# 09_USB_HUB.net
KiCad netlist of a schematic drawn in Altium Designer
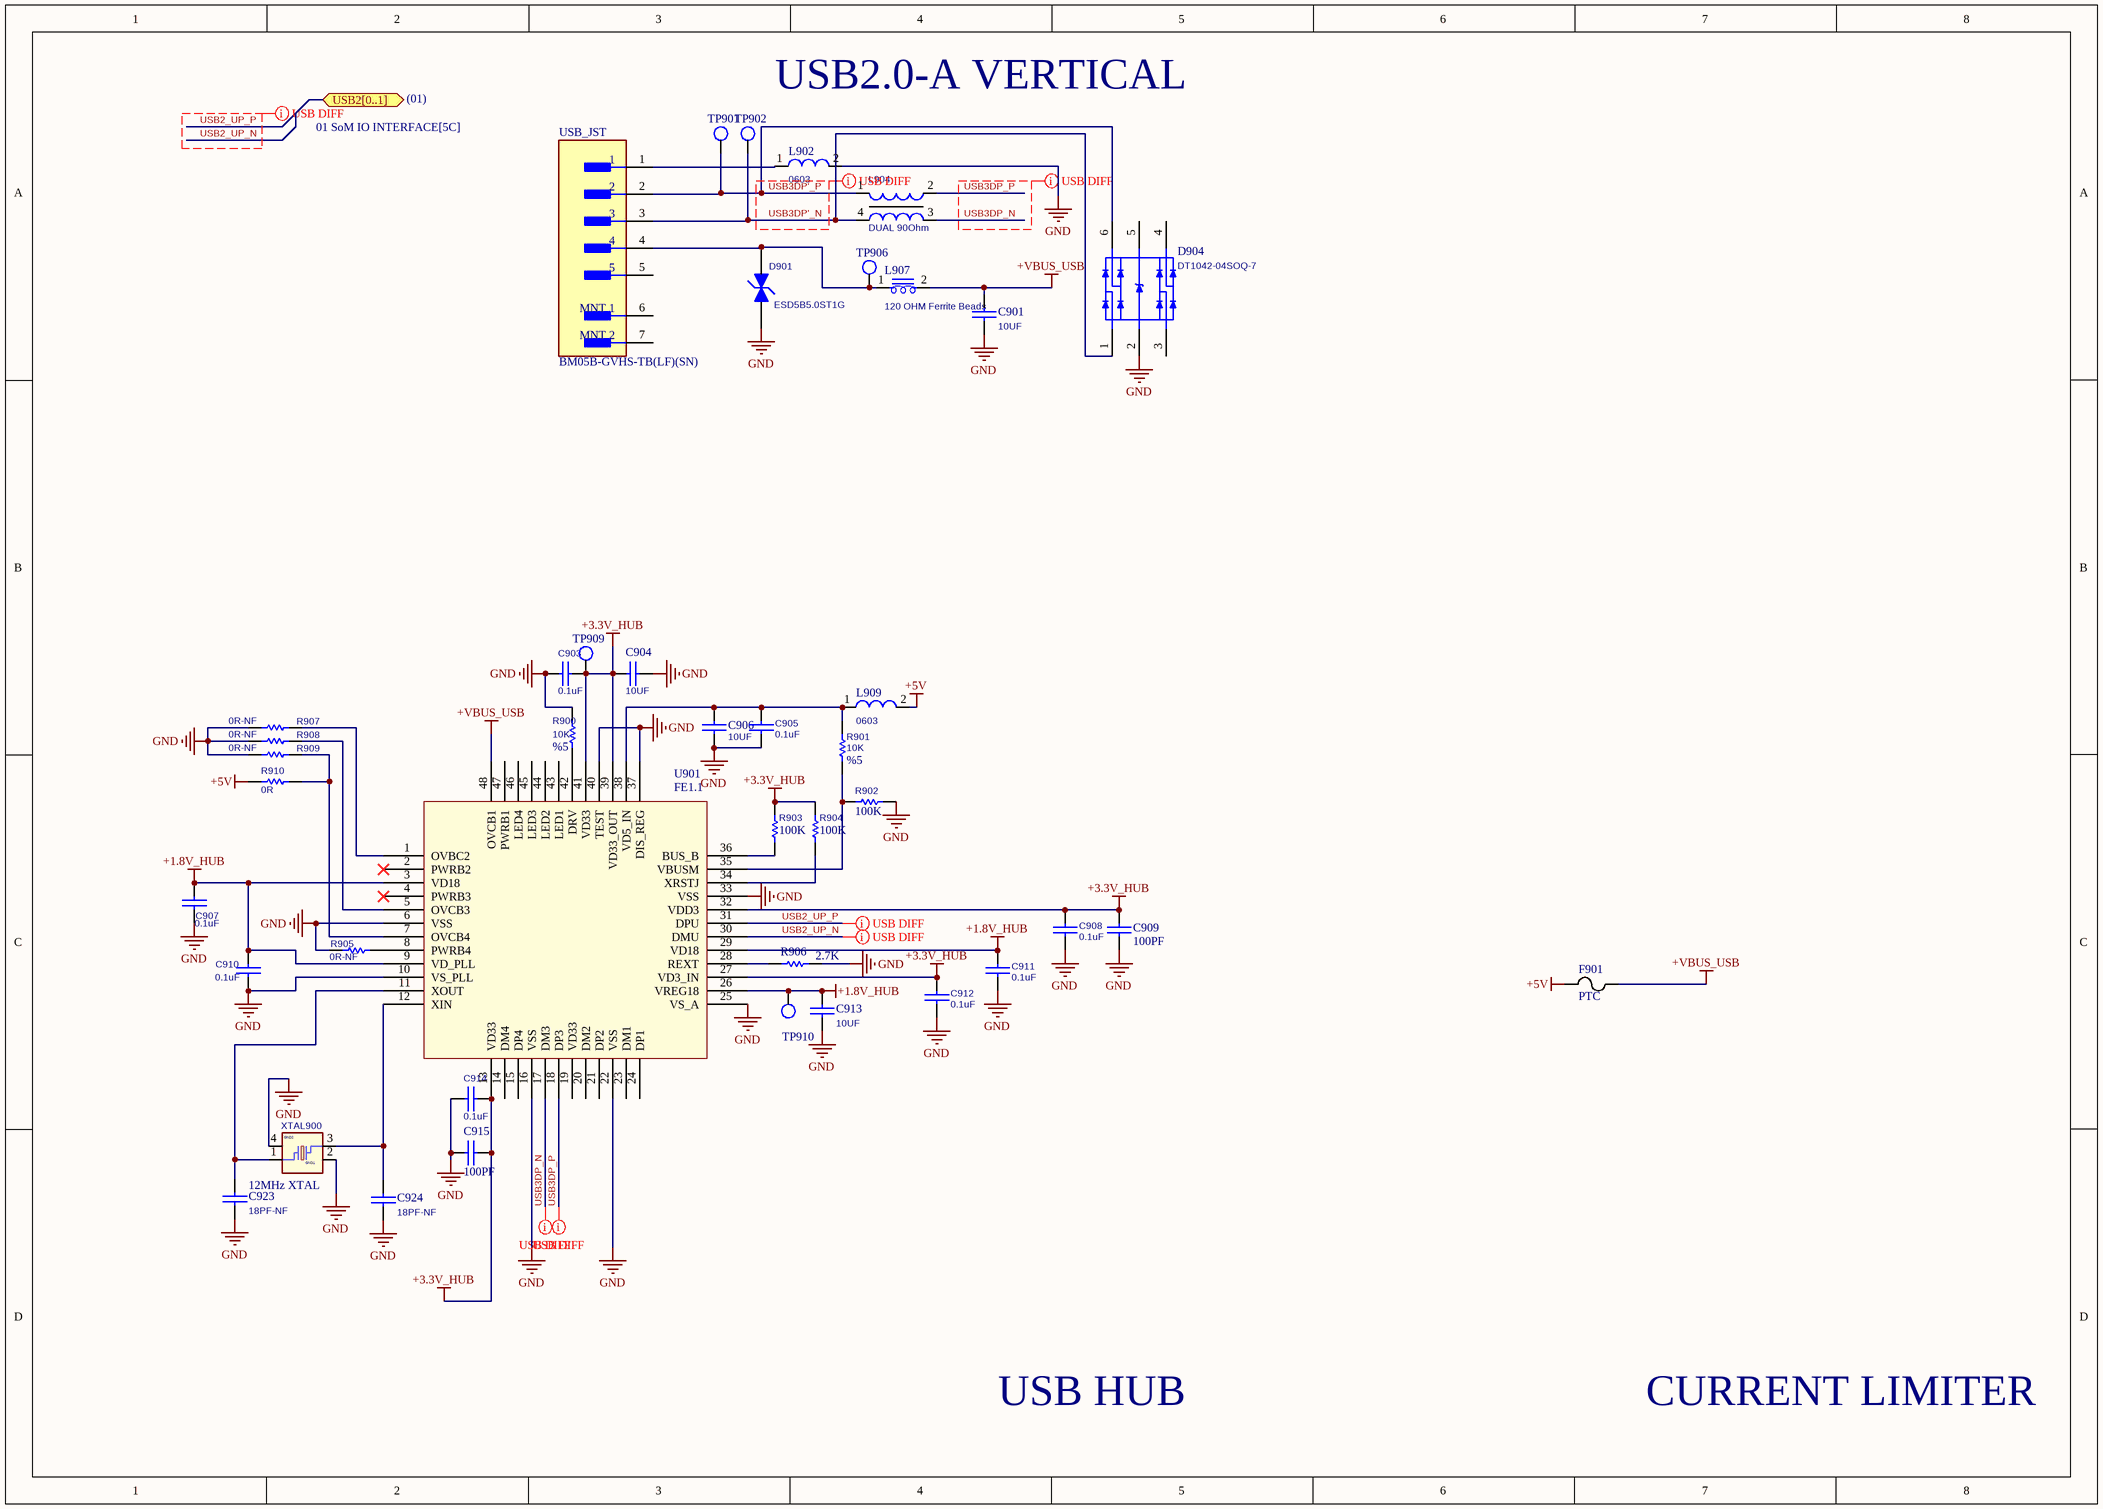
[diagram p0: 09 USB HUB.SchDoc]

(export (version "E")
  (design (tool "Eeschema 10.0.6"))
  (components
    (comp (ref "C901")
      (value "10UF")
      (footprint "0805")
      (description "CAP CER 10UF 16V X5R 0805")
      (fields (field (name "CREATED BY") "EE") (field (name "CHECKED BY") "*"))
      (libsource (lib "ARETE_SCH") (part "CAP-CL21A106KOQNNNG"))
    )
    (comp (ref "C903")
      (value "0.1uF")
      (footprint "0402_CC")
      (description "CAP VER 0.1UF 16V X7R 0402")
      (fields (field (name "CREATED BY") "LA") (field (name "CHECKED BY") "*"))
      (libsource (lib "ARETE_SCH") (part "CAP-CL05B104KO5NNNC"))
    )
    (comp (ref "C904")
      (value "10UF")
      (footprint "0805")
      (description "CAP CER 10UF 16V X5R 0805")
      (fields (field (name "CREATED BY") "EE") (field (name "CHECKED BY") "*"))
      (libsource (lib "ARETE_SCH") (part "CAP-CL21A106KOQNNNG"))
    )
    (comp (ref "C905")
      (value "0.1uF")
      (footprint "0402_CC")
      (description "CAP VER 0.1UF 16V X7R 0402")
      (fields (field (name "CREATED BY") "LA") (field (name "CHECKED BY") "*"))
      (libsource (lib "ARETE_SCH") (part "CAP-CL05B104KO5NNNC"))
    )
    (comp (ref "C906")
      (value "10UF")
      (footprint "0805")
      (description "CAP CER 10UF 16V X5R 0805")
      (fields (field (name "CREATED BY") "EE") (field (name "CHECKED BY") "*"))
      (libsource (lib "ARETE_SCH") (part "CAP-CL21A106KOQNNNG"))
    )
    (comp (ref "C907")
      (value "0.1uF")
      (footprint "0402_CC")
      (description "CAP VER 0.1UF 16V X7R 0402")
      (fields (field (name "CREATED BY") "LA") (field (name "CHECKED BY") "*"))
      (libsource (lib "ARETE_SCH") (part "CAP-CL05B104KO5NNNC"))
    )
    (comp (ref "C908")
      (value "0.1uF")
      (footprint "0402_CC")
      (description "CAP VER 0.1UF 16V X7R 0402")
      (fields (field (name "CREATED BY") "LA") (field (name "CHECKED BY") "*"))
      (libsource (lib "ARETE_SCH") (part "CAP-CL05B104KO5NNNC"))
    )
    (comp (ref "C909")
      (value "100PF")
      (footprint "0402_CC")
      (description "CAP CER 100PF 50V C0G/NPO 0402")
      (fields (field (name "CREATED BY") "*") (field (name "CHECKED BY") "*"))
      (libsource (lib "ARETE_SCH") (part "CAP-CC0402JRNPO9BN101"))
    )
    (comp (ref "C910")
      (value "0.1uF")
      (footprint "0402_CC")
      (description "CAP VER 0.1UF 16V X7R 0402")
      (fields (field (name "CREATED BY") "LA") (field (name "CHECKED BY") "*"))
      (libsource (lib "ARETE_SCH") (part "CAP-CL05B104KO5NNNC"))
    )
    (comp (ref "C911")
      (value "0.1uF")
      (footprint "0402_CC")
      (description "CAP VER 0.1UF 16V X7R 0402")
      (fields (field (name "CREATED BY") "LA") (field (name "CHECKED BY") "*"))
      (libsource (lib "ARETE_SCH") (part "CAP-CL05B104KO5NNNC"))
    )
    (comp (ref "C912")
      (value "0.1uF")
      (footprint "0402_CC")
      (description "CAP VER 0.1UF 16V X7R 0402")
      (fields (field (name "CREATED BY") "LA") (field (name "CHECKED BY") "*"))
      (libsource (lib "ARETE_SCH") (part "CAP-CL05B104KO5NNNC"))
    )
    (comp (ref "C913")
      (value "10UF")
      (footprint "0805")
      (description "CAP CER 10UF 16V X5R 0805")
      (fields (field (name "CREATED BY") "EE") (field (name "CHECKED BY") "*"))
      (libsource (lib "ARETE_SCH") (part "CAP-CL21A106KOQNNNG"))
    )
    (comp (ref "C914")
      (value "0.1uF")
      (footprint "0402_CC")
      (description "CAP VER 0.1UF 16V X7R 0402")
      (fields (field (name "CREATED BY") "LA") (field (name "CHECKED BY") "*"))
      (libsource (lib "ARETE_SCH") (part "CAP-CL05B104KO5NNNC"))
    )
    (comp (ref "C915")
      (value "100PF")
      (footprint "0402_CC")
      (description "CAP CER 100PF 50V C0G/NPO 0402")
      (fields (field (name "CREATED BY") "*") (field (name "CHECKED BY") "*"))
      (libsource (lib "ARETE_SCH") (part "CAP-CC0402JRNPO9BN101"))
    )
    (comp (ref "C923")
      (value "18PF-NF")
      (footprint "0402_CC")
      (description "CAP CER 18PF 50V C0G/NP0 0402")
      (fields (field (name "CREATED BY") "*") (field (name "CHECKED BY") "*"))
      (libsource (lib "ARETE_SCH") (part "CAP-GCM1555C1H180JA16D"))
    )
    (comp (ref "C924")
      (value "18PF-NF")
      (footprint "0402_CC")
      (description "CAP CER 18PF 50V C0G/NP0 0402")
      (fields (field (name "CREATED BY") "*") (field (name "CHECKED BY") "*"))
      (libsource (lib "ARETE_SCH") (part "CAP-GCM1555C1H180JA16D"))
    )
    (comp (ref "D901")
      (value "ESD5B5.0ST1G")
      (footprint "SOD523 - SZESD")
      (description "VS DIODE 5V SOD523")
      (fields (field (name "CREATED BY") "E.E") (field (name "CHECKED BY") "*"))
      (libsource (lib "ARETE_SCH") (part "DIODE-ESD5B5.0ST1G"))
    )
    (comp (ref "D904")
      (value "DT1042-04SOQ-7")
      (footprint "DIODE-DT1042-04SOQ-7")
      (description "HDMI TVS DIODE")
      (fields (field (name "CREATED BY") "E.E") (field (name "CHECKED BY") "*"))
      (libsource (lib "ARETE_SCH") (part "DIODE-DT1042-04SOQ-7"))
    )
    (comp (ref "F901")
      (value "PTC")
      (footprint "1812")
      (description "THERMISTOR PTC RESETTABLE FUSE 1206 1100mA 33V 1812")
      (fields (field (name "CREATED BY") "EE") (field (name "CHECKED BY") "*"))
      (libsource (lib "ARETE_V2_SCH") (part "FUSE-KMC5S110RY33"))
    )
    (comp (ref "L902")
      (value "0603")
      (footprint "0603_RES")
      (description "0OHM 0603")
      (fields (field (name "CREATED BY") "EE") (field (name "CHECKED BY") "*"))
      (libsource (lib "ARETE_SCH") (part "IND-FERRITE (RES 0 OHM) 0603"))
    )
    (comp (ref "L904")
      (value "DUAL 90Ohm")
      (footprint "DLW21H")
      (description "Common Mode Chokes Dual 90Ohm 100MHz 0.33A 0.35Ohm DCR SMD T/R")
      (fields (field (name "CREATED BY") "E.E") (field (name "CHECKED BY") "*"))
      (libsource (lib "ARETE_SCH") (part "IND-DLW21HN900SQ2L"))
    )
    (comp (ref "L907")
      (value "120 OHM Ferrite Beads")
      (footprint "0603_RES")
      (description "Ferrite Beads Multi-Layer 120Ohm 25% 100MHz 2A 0.05Ohm DCR 0603 Automotive T/R")
      (fields (field (name "CREATED BY") "E.E") (field (name "CHECKED BY") "*"))
      (libsource (lib "ARETE_SCH") (part "IND-BLM18PG121SH1D"))
    )
    (comp (ref "L909")
      (value "0603")
      (footprint "0603_RES")
      (description "0OHM 0603")
      (fields (field (name "CREATED BY") "EE") (field (name "CHECKED BY") "*"))
      (libsource (lib "ARETE_SCH") (part "IND-FERRITE (RES 0 OHM) 0603"))
    )
    (comp (ref "R900")
      (value "10K")
      (footprint "0402_RES")
      (description "RES 10K OHM 5% 1/16W 0402")
      (fields
        (field (name "TOLERANCE") "%5")
        (field (name "CREATED BY") "LA")
        (field (name "CHECKED BY") "*")
      )
      (libsource (lib "ARETE_SCH") (part "RES-RMCF0402JT10K0"))
    )
    (comp (ref "R901")
      (value "10K")
      (footprint "0402_RES")
      (description "RES 10K OHM 5% 1/16W 0402")
      (fields
        (field (name "TOLERANCE") "%5")
        (field (name "CREATED BY") "LA")
        (field (name "CHECKED BY") "*")
      )
      (libsource (lib "ARETE_SCH") (part "RES-RMCF0402JT10K0"))
    )
    (comp (ref "R902")
      (value "100K")
      (footprint "0402_RES")
      (description "RES 100K OHM 5% 1/16W 0402")
      (fields
        (field (name "TOLERANCE") "%5")
        (field (name "CREATED BY") "LA")
        (field (name "CHECKED BY") "*")
      )
      (libsource (lib "ARETE_SCH") (part "RES-RMCF0402JT100K"))
    )
    (comp (ref "R903")
      (value "100K")
      (footprint "0402_RES")
      (description "RES 100K OHM 5% 1/16W 0402")
      (fields
        (field (name "TOLERANCE") "%5")
        (field (name "CREATED BY") "LA")
        (field (name "CHECKED BY") "*")
      )
      (libsource (lib "ARETE_SCH") (part "RES-RMCF0402JT100K"))
    )
    (comp (ref "R904")
      (value "100K")
      (footprint "0402_RES")
      (description "RES 100K OHM 5% 1/16W 0402")
      (fields
        (field (name "TOLERANCE") "%5")
        (field (name "CREATED BY") "LA")
        (field (name "CHECKED BY") "*")
      )
      (libsource (lib "ARETE_SCH") (part "RES-RMCF0402JT100K"))
    )
    (comp (ref "R905")
      (value "0R-NF")
      (footprint "0402_RES")
      (description "RES 0 OHM JUMPER 1/16W 0402")
      (fields (field (name "CREATED BY") "LA") (field (name "CHECKED BY") "*"))
      (libsource (lib "ARETE_SCH") (part "RES-RMCF0402ZT0R00"))
    )
    (comp (ref "R906")
      (value "2.7K")
      (footprint "0402_RES")
      (description "RES SMD 2.7K OHM 1% 1/16W 0402")
      (fields (field (name "CREATED BY") "EE") (field (name "CHECKED BY") "*"))
      (libsource (lib "ARETE_V2_SCH") (part "RES-RMCF0402FT2K70"))
    )
    (comp (ref "R907")
      (value "0R-NF")
      (footprint "0402_RES")
      (description "RES 0 OHM JUMPER 1/16W 0402")
      (fields (field (name "CREATED BY") "LA") (field (name "CHECKED BY") "*"))
      (libsource (lib "ARETE_SCH") (part "RES-RMCF0402ZT0R00"))
    )
    (comp (ref "R908")
      (value "0R-NF")
      (footprint "0402_RES")
      (description "RES 0 OHM JUMPER 1/16W 0402")
      (fields (field (name "CREATED BY") "LA") (field (name "CHECKED BY") "*"))
      (libsource (lib "ARETE_SCH") (part "RES-RMCF0402ZT0R00"))
    )
    (comp (ref "R909")
      (value "0R-NF")
      (footprint "0402_RES")
      (description "RES 0 OHM JUMPER 1/16W 0402")
      (fields (field (name "CREATED BY") "LA") (field (name "CHECKED BY") "*"))
      (libsource (lib "ARETE_SCH") (part "RES-RMCF0402ZT0R00"))
    )
    (comp (ref "R910")
      (value "0R")
      (footprint "0402_RES")
      (description "RES 0 OHM JUMPER 1/16W 0402")
      (fields (field (name "CREATED BY") "LA") (field (name "CHECKED BY") "*"))
      (libsource (lib "ARETE_SCH") (part "RES-RMCF0402ZT0R00"))
    )
    (comp (ref "TP901")
      (value "TEST POINT 15")
      (footprint "testpoint_15")
      (libsource (lib "X98_CARRIER_V1R2") (part "TEST POINT 15"))
    )
    (comp (ref "TP902")
      (value "TEST POINT 15")
      (footprint "testpoint_15")
      (libsource (lib "X98_CARRIER_V1R2") (part "TEST POINT 15"))
    )
    (comp (ref "TP906")
      (value "TEST POINT 15")
      (footprint "testpoint_15")
      (libsource (lib "X98_CARRIER_V1R2") (part "TEST POINT 15"))
    )
    (comp (ref "TP909")
      (value "TEST POINT 15")
      (footprint "testpoint_15")
      (libsource (lib "X98_CARRIER_V1R2") (part "TEST POINT 15"))
    )
    (comp (ref "TP910")
      (value "TEST POINT 15")
      (footprint "testpoint_15")
      (libsource (lib "X98_CARRIER_V1R2") (part "TEST POINT 15"))
    )
    (comp (ref "U901")
      (value "FE1.1")
      (footprint "LQFP48")
      (description "IC 4XCH USB Hub Controller USB 2.0 USB Interface 48-QFP (7x7)")
      (fields (field (name "CREATED BY") "OKS") (field (name "CHECKED BY") "*"))
      (libsource (lib "ARETE_V2_SCH") (part "IC-FE1.1-AQFP48A"))
    )
    (comp (ref "USB_JST")
      (value "BM05B-GVHS-TB(LF)(SN)")
      (footprint "FP-BM05B-GVHS-TB_LF_SN-MFG")
      (description "CONN HEADER SMD 5POS 1.25MM")
      (libsource (lib "Altium Content Vault") (part "a8463467369b6bfccc80258e24cb490"))
    )
    (comp (ref "XTAL900")
      (value "CRYSTAL 12.MHZ 18PF SMD")
      (footprint "XTLOSC4_3P2X2P5MM_SM")
      (description "CRYSTAL 12.0000MHZ 18PF SMD")
      (fields (field (name "CREATED BY") "E.E") (field (name "CHECKED BY") "*"))
      (libsource (lib "ARETE_SCH") (part "XTAL-FA-238V 12.0000MB50X-C0"))
    )
  )
  (nets
    (net (code "3") (name "+1.8V_HUB") (class "Default")
      (node (ref "C907") (pin "1") (pinfunction "1_1") (pintype "passive"))
      (node (ref "C910") (pin "1") (pinfunction "1_1") (pintype "passive"))
      (node (ref "C911") (pin "2") (pinfunction "2_2") (pintype "passive"))
      (node (ref "C913") (pin "1") (pinfunction "1_1") (pintype "passive"))
      (node (ref "TP910") (pin "1") (pinfunction "1_1") (pintype "passive"))
      (node (ref "U901") (pin "26") (pinfunction "VREG18_26") (pintype "passive"))
      (node (ref "U901") (pin "29") (pinfunction "VD18_29") (pintype "passive"))
      (node (ref "U901") (pin "3") (pinfunction "VD18_3") (pintype "passive"))
      (node (ref "U901") (pin "9") (pinfunction "VD_PLL_9") (pintype "passive"))
    )
    (net (code "4") (name "+3.3V_HUB") (class "Default")
      (node (ref "C903") (pin "1") (pinfunction "1_1") (pintype "passive"))
      (node (ref "C904") (pin "1") (pinfunction "1_1") (pintype "passive"))
      (node (ref "C908") (pin "2") (pinfunction "2_2") (pintype "passive"))
      (node (ref "C909") (pin "2") (pinfunction "2_2") (pintype "passive"))
      (node (ref "C912") (pin "2") (pinfunction "2_2") (pintype "passive"))
      (node (ref "C914") (pin "2") (pinfunction "2_2") (pintype "passive"))
      (node (ref "C915") (pin "2") (pinfunction "2_2") (pintype "passive"))
      (node (ref "R903") (pin "2") (pinfunction "2_2") (pintype "passive"))
      (node (ref "R904") (pin "2") (pinfunction "2_2") (pintype "passive"))
      (node (ref "TP909") (pin "1") (pinfunction "1_1") (pintype "passive"))
      (node (ref "U901") (pin "13") (pinfunction "VD33_13") (pintype "passive"))
      (node (ref "U901") (pin "27") (pinfunction "VD3_IN_27") (pintype "passive"))
      (node (ref "U901") (pin "32") (pinfunction "VDD3_32") (pintype "passive"))
      (node (ref "U901") (pin "39") (pinfunction "VD33_OUT_39") (pintype "passive"))
      (node (ref "U901") (pin "41") (pinfunction "VD33_41") (pintype "passive"))
    )
    (net (code "5") (name "+5V") (class "Default")
      (node (ref "F901") (pin "1") (pinfunction "1_1") (pintype "passive"))
      (node (ref "L909") (pin "2") (pinfunction "2_2") (pintype "passive"))
      (node (ref "R910") (pin "2") (pinfunction "2_2") (pintype "passive"))
    )
    (net (code "6") (name "+VBUS_USB") (class "Default")
      (node (ref "C901") (pin "1") (pinfunction "1_1") (pintype "passive"))
      (node (ref "F901") (pin "2") (pinfunction "2_2") (pintype "passive"))
      (node (ref "L907") (pin "2") (pinfunction "2_2") (pintype "passive"))
      (node (ref "U901") (pin "48") (pinfunction "OVCB1_48") (pintype "passive"))
    )
    (net (code "8") (name "/USB2_UP_N") (class "Default")
      (node (ref "U901") (pin "30") (pinfunction "DMU_30") (pintype "passive"))
    )
    (net (code "9") (name "/USB2_UP_P") (class "Default")
      (node (ref "U901") (pin "31") (pinfunction "DPU_31") (pintype "passive"))
    )
    (net (code "10") (name "/USB3DP'_N") (class "Default")
      (node (ref "D904") (pin "1") (pinfunction "IO1_1") (pintype "passive"))
      (node (ref "L904") (pin "4") (pinfunction "4_4") (pintype "passive"))
      (node (ref "TP902") (pin "1") (pinfunction "1_1") (pintype "passive"))
      (node (ref "USB_JST") (pin "3") (pinfunction "3_3") (pintype "passive"))
    )
    (net (code "11") (name "/USB3DP'_P") (class "Default")
      (node (ref "D904") (pin "6") (pinfunction "IO4_6") (pintype "passive"))
      (node (ref "L904") (pin "1") (pinfunction "1_1") (pintype "passive"))
      (node (ref "TP901") (pin "1") (pinfunction "1_1") (pintype "passive"))
      (node (ref "USB_JST") (pin "2") (pinfunction "2_2") (pintype "passive"))
    )
    (net (code "12") (name "/USB3DP_N") (class "Default")
      (node (ref "L904") (pin "3") (pinfunction "3_3") (pintype "passive"))
      (node (ref "U901") (pin "17") (pinfunction "DM3_17") (pintype "passive"))
    )
    (net (code "13") (name "/USB3DP_P") (class "Default")
      (node (ref "L904") (pin "2") (pinfunction "2_2") (pintype "passive"))
      (node (ref "U901") (pin "18") (pinfunction "DP3_18") (pintype "passive"))
    )
    (net (code "14") (name "GND") (class "Default")
      (node (ref "C901") (pin "2") (pinfunction "2_2") (pintype "passive"))
      (node (ref "C903") (pin "2") (pinfunction "2_2") (pintype "passive"))
      (node (ref "C904") (pin "2") (pinfunction "2_2") (pintype "passive"))
      (node (ref "C905") (pin "1") (pinfunction "1_1") (pintype "passive"))
      (node (ref "C906") (pin "1") (pinfunction "1_1") (pintype "passive"))
      (node (ref "C907") (pin "2") (pinfunction "2_2") (pintype "passive"))
      (node (ref "C908") (pin "1") (pinfunction "1_1") (pintype "passive"))
      (node (ref "C909") (pin "1") (pinfunction "1_1") (pintype "passive"))
      (node (ref "C910") (pin "2") (pinfunction "2_2") (pintype "passive"))
      (node (ref "C911") (pin "1") (pinfunction "1_1") (pintype "passive"))
      (node (ref "C912") (pin "1") (pinfunction "1_1") (pintype "passive"))
      (node (ref "C913") (pin "2") (pinfunction "2_2") (pintype "passive"))
      (node (ref "C914") (pin "1") (pinfunction "1_1") (pintype "passive"))
      (node (ref "C915") (pin "1") (pinfunction "1_1") (pintype "passive"))
      (node (ref "C923") (pin "2") (pinfunction "2_2") (pintype "passive"))
      (node (ref "C924") (pin "2") (pinfunction "2_2") (pintype "passive"))
      (node (ref "D901") (pin "1") (pinfunction "A_1") (pintype "passive"))
      (node (ref "D904") (pin "2") (pinfunction "VSS_2") (pintype "power_in"))
      (node (ref "L902") (pin "2") (pinfunction "2_2") (pintype "passive"))
      (node (ref "R900") (pin "1") (pinfunction "1_1") (pintype "passive"))
      (node (ref "R902") (pin "1") (pinfunction "1_1") (pintype "passive"))
      (node (ref "R905") (pin "1") (pinfunction "1_1") (pintype "passive"))
      (node (ref "R906") (pin "2") (pinfunction "2_2") (pintype "passive"))
      (node (ref "R907") (pin "1") (pinfunction "1_1") (pintype "passive"))
      (node (ref "R908") (pin "1") (pinfunction "1_1") (pintype "passive"))
      (node (ref "R909") (pin "1") (pinfunction "1_1") (pintype "passive"))
      (node (ref "U901") (pin "10") (pinfunction "VS_PLL_10") (pintype "passive"))
      (node (ref "U901") (pin "16") (pinfunction "VSS_16") (pintype "passive"))
      (node (ref "U901") (pin "22") (pinfunction "VSS_22") (pintype "passive"))
      (node (ref "U901") (pin "25") (pinfunction "VS_A_25") (pintype "passive"))
      (node (ref "U901") (pin "33") (pinfunction "VSS_33") (pintype "passive"))
      (node (ref "U901") (pin "37") (pinfunction "DIS_REG_37") (pintype "passive"))
      (node (ref "U901") (pin "40") (pinfunction "TEST_40") (pintype "passive"))
      (node (ref "U901") (pin "6") (pinfunction "VSS_6") (pintype "passive"))
      (node (ref "XTAL900") (pin "2") (pinfunction "GND1_2") (pintype "power_in"))
      (node (ref "XTAL900") (pin "4") (pinfunction "GND2_4") (pintype "power_in"))
    )
    (net (code "15") (name "Net-(D901-K)") (class "Default")
      (node (ref "D901") (pin "2") (pinfunction "K_2") (pintype "passive"))
      (node (ref "L907") (pin "1") (pinfunction "1_1") (pintype "passive"))
      (node (ref "TP906") (pin "1") (pinfunction "1_1") (pintype "passive"))
      (node (ref "USB_JST") (pin "4") (pinfunction "4_4") (pintype "passive"))
    )
    (net (code "16") (name "Net-(L902-Pad1)") (class "Default")
      (node (ref "L902") (pin "1") (pinfunction "1_1") (pintype "passive"))
      (node (ref "USB_JST") (pin "1") (pinfunction "1_1") (pintype "passive"))
    )
    (net (code "17") (name "Net-(U901-BUS_B)") (class "Default")
      (node (ref "R903") (pin "1") (pinfunction "1_1") (pintype "passive"))
      (node (ref "U901") (pin "36") (pinfunction "BUS_B_36") (pintype "passive"))
    )
    (net (code "18") (name "Net-(U901-DRV)") (class "Default")
      (node (ref "R900") (pin "2") (pinfunction "2_2") (pintype "passive"))
      (node (ref "U901") (pin "42") (pinfunction "DRV_42") (pintype "passive"))
    )
    (net (code "19") (name "Net-(U901-OVBC2)") (class "Default")
      (node (ref "R907") (pin "2") (pinfunction "2_2") (pintype "passive"))
      (node (ref "U901") (pin "1") (pinfunction "OVBC2_1") (pintype "passive"))
    )
    (net (code "20") (name "Net-(U901-OVCB3)") (class "Default")
      (node (ref "R908") (pin "2") (pinfunction "2_2") (pintype "passive"))
      (node (ref "U901") (pin "5") (pinfunction "OVCB3_5") (pintype "passive"))
    )
    (net (code "21") (name "Net-(U901-OVCB4)") (class "Default")
      (node (ref "R909") (pin "2") (pinfunction "2_2") (pintype "passive"))
      (node (ref "R910") (pin "1") (pinfunction "1_1") (pintype "passive"))
      (node (ref "U901") (pin "7") (pinfunction "OVCB4_7") (pintype "passive"))
    )
    (net (code "22") (name "Net-(U901-PWRB4)") (class "Default")
      (node (ref "R905") (pin "2") (pinfunction "2_2") (pintype "passive"))
      (node (ref "U901") (pin "8") (pinfunction "PWRB4_8") (pintype "passive"))
    )
    (net (code "23") (name "Net-(U901-REXT)") (class "Default")
      (node (ref "R906") (pin "1") (pinfunction "1_1") (pintype "passive"))
      (node (ref "U901") (pin "28") (pinfunction "REXT_28") (pintype "passive"))
    )
    (net (code "24") (name "Net-(U901-VBUSM)") (class "Default")
      (node (ref "R901") (pin "1") (pinfunction "1_1") (pintype "passive"))
      (node (ref "R902") (pin "2") (pinfunction "2_2") (pintype "passive"))
      (node (ref "U901") (pin "35") (pinfunction "VBUSM_35") (pintype "passive"))
    )
    (net (code "25") (name "Net-(U901-VD5_IN)") (class "Default")
      (node (ref "C905") (pin "2") (pinfunction "2_2") (pintype "passive"))
      (node (ref "C906") (pin "2") (pinfunction "2_2") (pintype "passive"))
      (node (ref "L909") (pin "1") (pinfunction "1_1") (pintype "passive"))
      (node (ref "R901") (pin "2") (pinfunction "2_2") (pintype "passive"))
      (node (ref "U901") (pin "38") (pinfunction "VD5_IN_38") (pintype "passive"))
    )
    (net (code "26") (name "Net-(U901-XIN)") (class "Default")
      (node (ref "C924") (pin "1") (pinfunction "1_1") (pintype "passive"))
      (node (ref "U901") (pin "12") (pinfunction "XIN_12") (pintype "passive"))
      (node (ref "XTAL900") (pin "3") (pinfunction "3_3") (pintype "passive"))
    )
    (net (code "27") (name "Net-(U901-XOUT)") (class "Default")
      (node (ref "C923") (pin "1") (pinfunction "1_1") (pintype "passive"))
      (node (ref "U901") (pin "11") (pinfunction "XOUT_11") (pintype "passive"))
      (node (ref "XTAL900") (pin "1") (pinfunction "1_1") (pintype "passive"))
    )
    (net (code "28") (name "Net-(U901-XRSTJ)") (class "Default")
      (node (ref "R904") (pin "1") (pinfunction "1_1") (pintype "passive"))
      (node (ref "U901") (pin "34") (pinfunction "XRSTJ_34") (pintype "passive"))
    )
    (net (code "29") (name "unconnected-(D904-IO2-Pad3)") (class "Default")
      (node (ref "D904") (pin "3") (pinfunction "IO2_3") (pintype "passive"))
    )
    (net (code "30") (name "unconnected-(D904-IO3-Pad4)") (class "Default")
      (node (ref "D904") (pin "4") (pinfunction "IO3_4") (pintype "passive"))
    )
    (net (code "31") (name "unconnected-(D904-VCC-Pad5)") (class "Default")
      (node (ref "D904") (pin "5") (pinfunction "VCC_5") (pintype "power_in"))
    )
    (net (code "32") (name "unconnected-(U901-DM1-Pad23)") (class "Default")
      (node (ref "U901") (pin "23") (pinfunction "DM1_23") (pintype "passive"))
    )
    (net (code "33") (name "unconnected-(U901-DM2-Pad20)") (class "Default")
      (node (ref "U901") (pin "20") (pinfunction "DM2_20") (pintype "passive"))
    )
    (net (code "34") (name "unconnected-(U901-DM4-Pad14)") (class "Default")
      (node (ref "U901") (pin "14") (pinfunction "DM4_14") (pintype "passive"))
    )
    (net (code "35") (name "unconnected-(U901-DP1-Pad24)") (class "Default")
      (node (ref "U901") (pin "24") (pinfunction "DP1_24") (pintype "passive"))
    )
    (net (code "36") (name "unconnected-(U901-DP2-Pad21)") (class "Default")
      (node (ref "U901") (pin "21") (pinfunction "DP2_21") (pintype "passive"))
    )
    (net (code "37") (name "unconnected-(U901-DP4-Pad15)") (class "Default")
      (node (ref "U901") (pin "15") (pinfunction "DP4_15") (pintype "passive"))
    )
    (net (code "38") (name "unconnected-(U901-LED1-Pad43)") (class "Default")
      (node (ref "U901") (pin "43") (pinfunction "LED1_43") (pintype "passive"))
    )
    (net (code "39") (name "unconnected-(U901-LED2-Pad44)") (class "Default")
      (node (ref "U901") (pin "44") (pinfunction "LED2_44") (pintype "passive"))
    )
    (net (code "40") (name "unconnected-(U901-LED3-Pad45)") (class "Default")
      (node (ref "U901") (pin "45") (pinfunction "LED3_45") (pintype "passive"))
    )
    (net (code "41") (name "unconnected-(U901-LED4-Pad46)") (class "Default")
      (node (ref "U901") (pin "46") (pinfunction "LED4_46") (pintype "passive"))
    )
    (net (code "42") (name "unconnected-(U901-PWRB1-Pad47)") (class "Default")
      (node (ref "U901") (pin "47") (pinfunction "PWRB1_47") (pintype "passive"))
    )
    (net (code "43") (name "unconnected-(U901-PWRB2-Pad2)") (class "Default")
      (node (ref "U901") (pin "2") (pinfunction "PWRB2_2") (pintype "passive+no_connect"))
    )
    (net (code "44") (name "unconnected-(U901-PWRB3-Pad4)") (class "Default")
      (node (ref "U901") (pin "4") (pinfunction "PWRB3_4") (pintype "passive+no_connect"))
    )
    (net (code "45") (name "unconnected-(U901-VD33-Pad19)") (class "Default")
      (node (ref "U901") (pin "19") (pinfunction "VD33_19") (pintype "passive"))
    )
    (net (code "46") (name "unconnected-(USB_JST-MNT_1-Pad6)") (class "Default")
      (node (ref "USB_JST") (pin "6") (pinfunction "MNT_1_6") (pintype "passive"))
    )
    (net (code "47") (name "unconnected-(USB_JST-MNT_2-Pad7)") (class "Default")
      (node (ref "USB_JST") (pin "7") (pinfunction "MNT_2_7") (pintype "passive"))
    )
    (net (code "48") (name "unconnected-(USB_JST-Pad5)") (class "Default")
      (node (ref "USB_JST") (pin "5") (pinfunction "5_5") (pintype "passive"))
    )
  )
)
